# Relay_01.net
KiCad netlist of a schematic drawn in Altium Designer
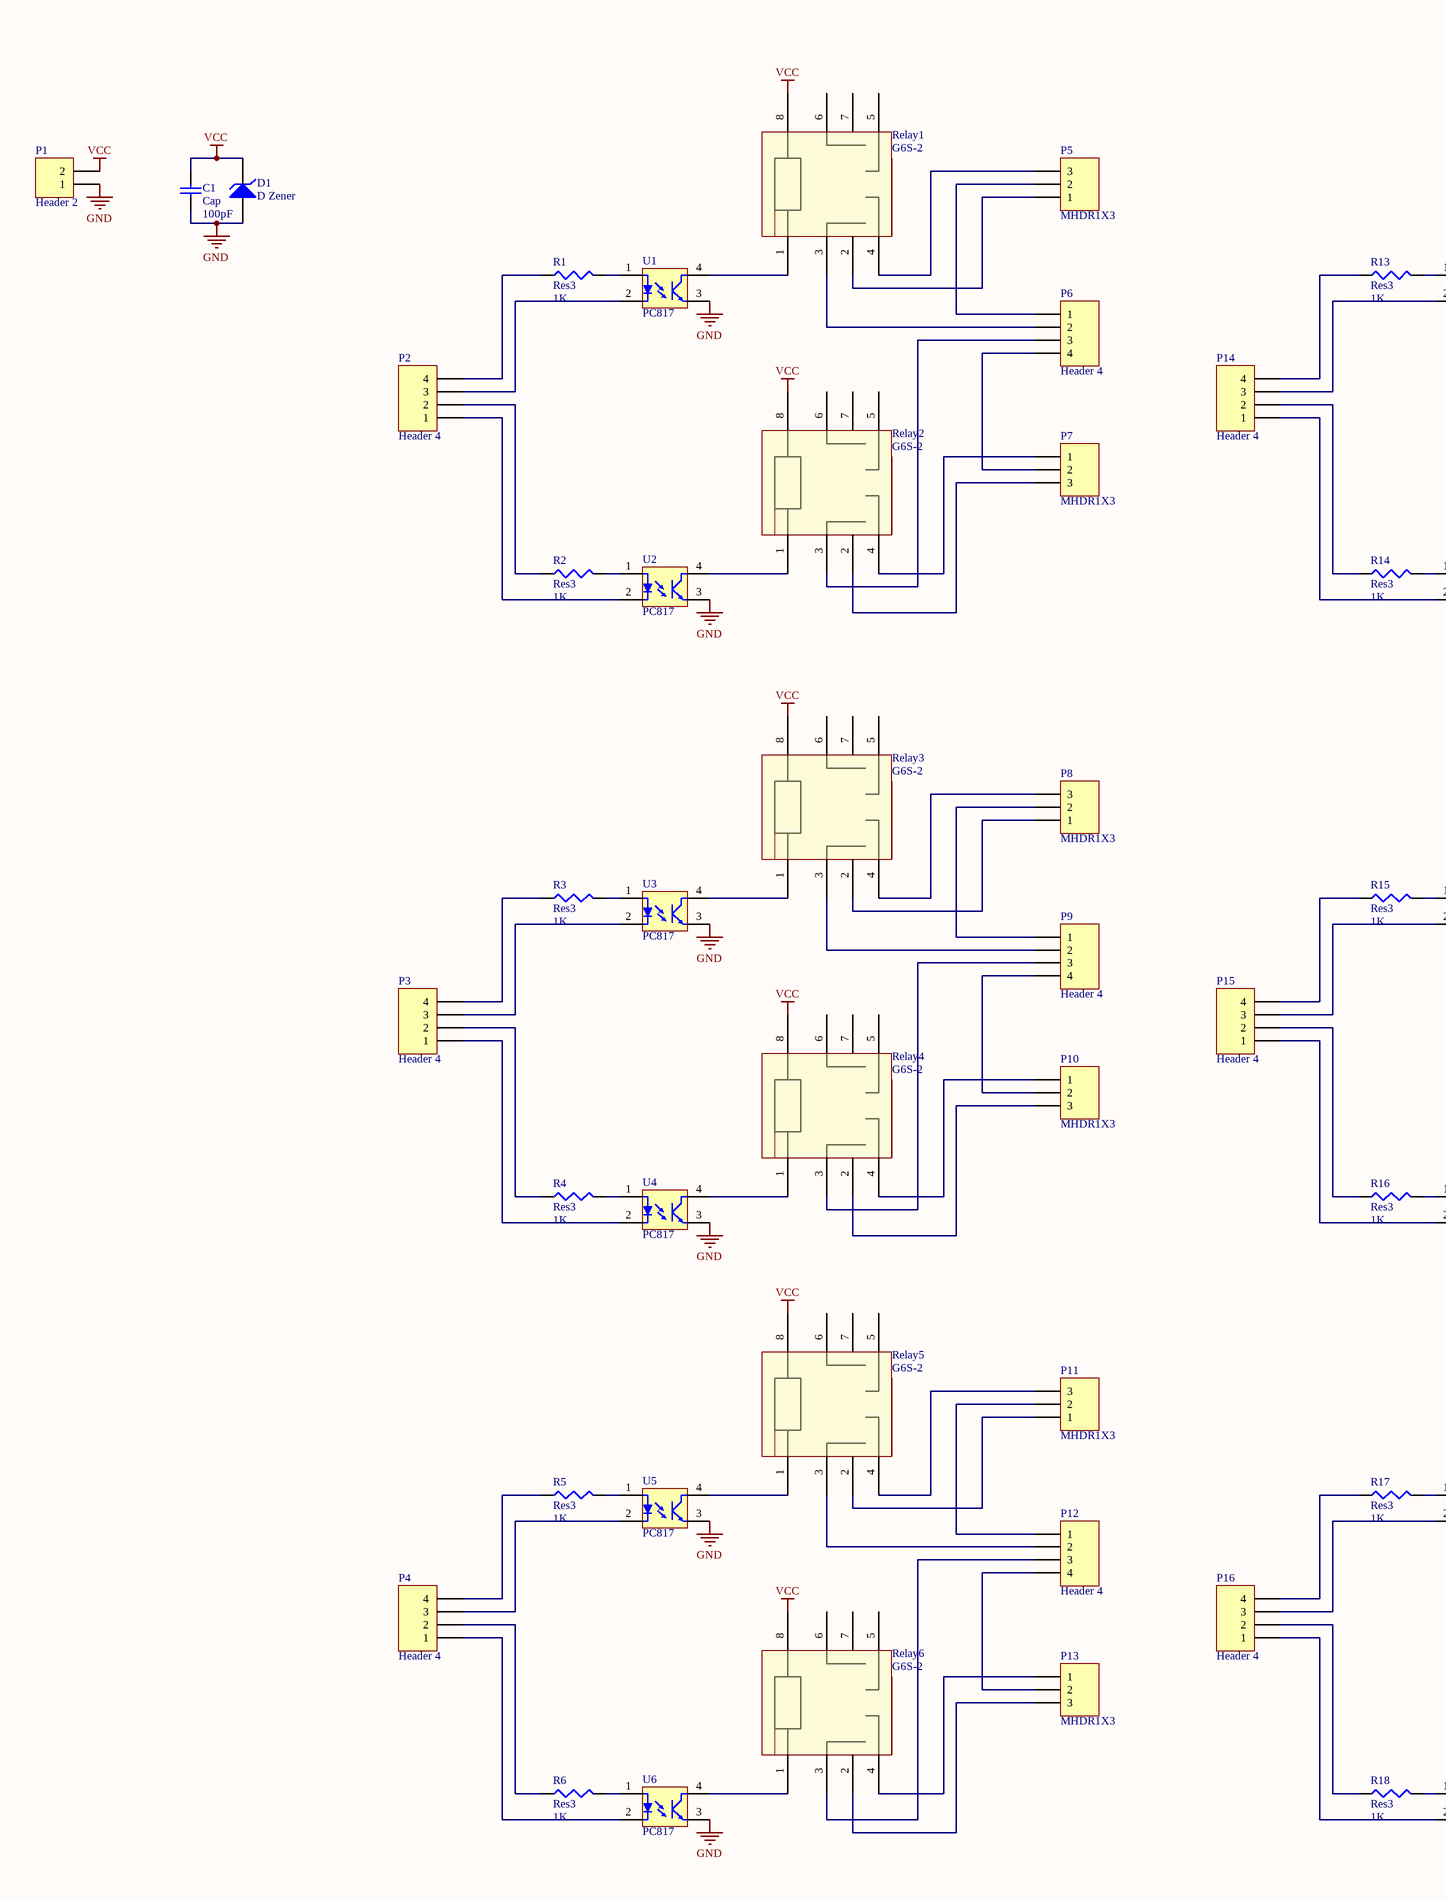
[diagram p0: Relay 01.SchDoc, left]
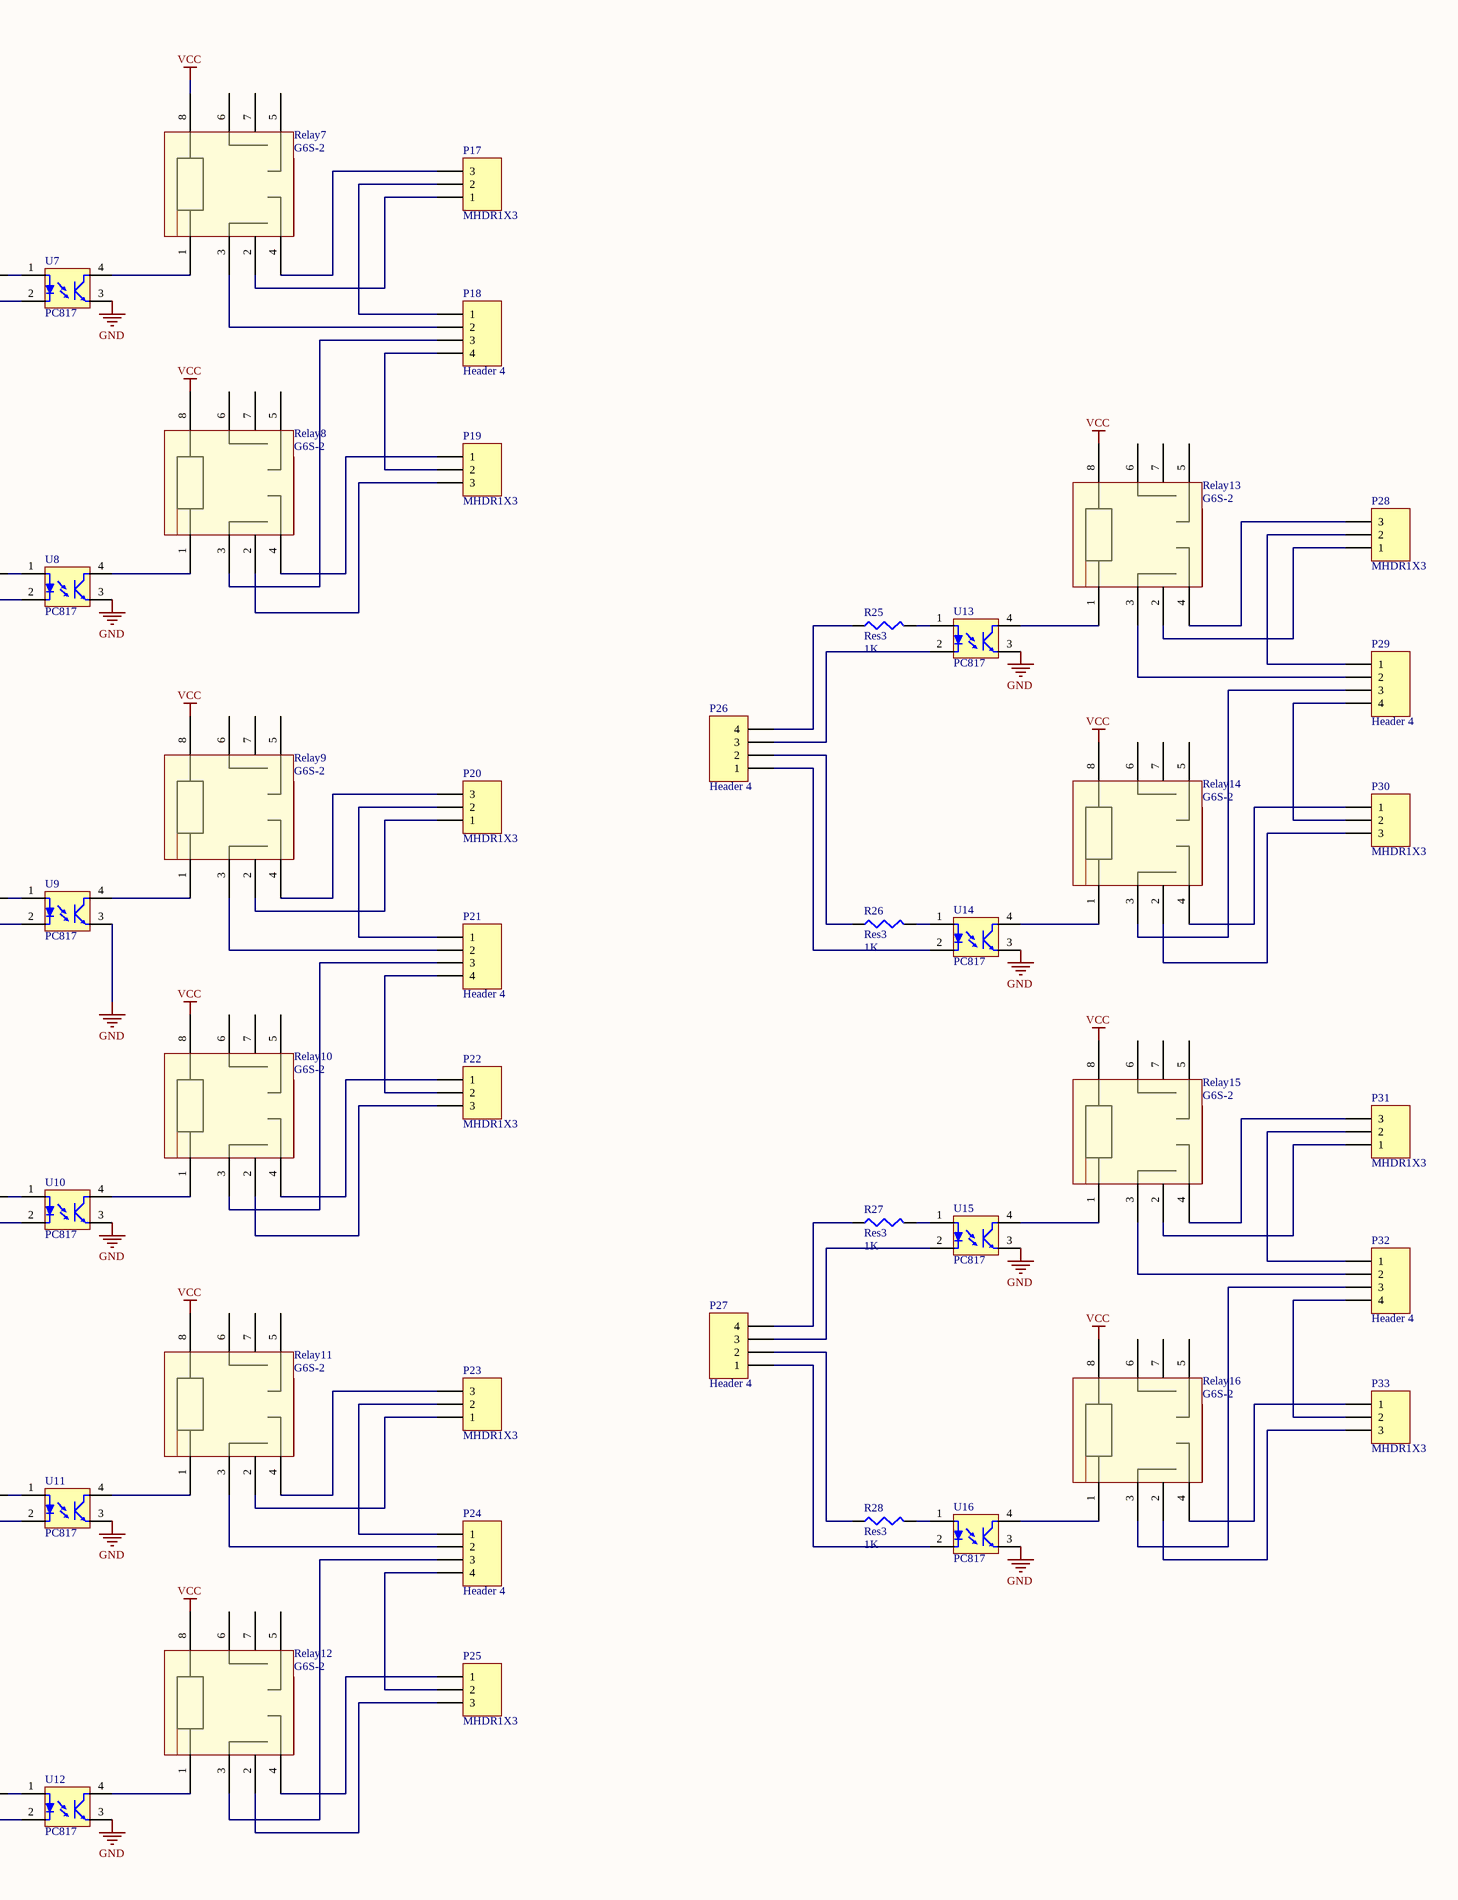
[diagram p1: Relay 01.SchDoc, right]

(export (version "E")
  (design (tool "Eeschema 10.0.6"))
  (components
    (comp (ref "C1")
      (value "Cap")
      (footprint "RAD-0.3")
      (description "Capacitor")
      (fields (field (name "ALTIUM_VALUE") "100pF") (field (name "PUBLISHER") "Altium Limited"))
      (libsource (lib "Miscellaneous Devices") (part "Cap"))
    )
    (comp (ref "D1")
      (value "D Zener")
      (footprint "DIODE-0.7")
      (description "Zener Diode")
      (fields (field (name "PUBLISHER") "Altium Limited"))
      (libsource (lib "Miscellaneous Devices") (part "D Zener"))
    )
    (comp (ref "P1")
      (value "Header 2")
      (footprint "CON2")
      (description "Header, 2-Pin")
      (fields (field (name "PUBLISHER") "Altium Limited"))
      (libsource (lib "Miscellaneous Connectors") (part "Header 2"))
    )
    (comp (ref "P2")
      (value "Header 4")
      (footprint "CON4")
      (description "Header, 4-Pin")
      (fields (field (name "PUBLISHER") "Altium Limited"))
      (libsource (lib "") (part "Header 4_1"))
    )
    (comp (ref "P3")
      (value "Header 4")
      (footprint "CON4")
      (description "Header, 4-Pin")
      (fields (field (name "PUBLISHER") "Altium Limited"))
      (libsource (lib "") (part "Header 4_1"))
    )
    (comp (ref "P4")
      (value "Header 4")
      (footprint "CON4")
      (description "Header, 4-Pin")
      (fields (field (name "PUBLISHER") "Altium Limited"))
      (libsource (lib "") (part "Header 4_1"))
    )
    (comp (ref "P5")
      (value "MHDR1X3")
      (footprint "HDR1X3")
      (description "Header, 3-Pin")
      (fields (field (name "PUBLISHER") "Altium Limited"))
      (libsource (lib "Miscellaneous Connectors") (part "MHDR1X3"))
    )
    (comp (ref "P6")
      (value "Header 4")
      (footprint "CON4")
      (description "Header, 4-Pin")
      (fields (field (name "PUBLISHER") "Altium Limited"))
      (libsource (lib "Miscellaneous Connectors") (part "Header 4"))
    )
    (comp (ref "P7")
      (value "MHDR1X3")
      (footprint "HDR1X3")
      (description "Header, 3-Pin")
      (fields (field (name "PUBLISHER") "Altium Limited"))
      (libsource (lib "") (part "MHDR1X3_1"))
    )
    (comp (ref "P8")
      (value "MHDR1X3")
      (footprint "HDR1X3")
      (description "Header, 3-Pin")
      (fields (field (name "PUBLISHER") "Altium Limited"))
      (libsource (lib "Miscellaneous Connectors") (part "MHDR1X3"))
    )
    (comp (ref "P9")
      (value "Header 4")
      (footprint "CON4")
      (description "Header, 4-Pin")
      (fields (field (name "PUBLISHER") "Altium Limited"))
      (libsource (lib "Miscellaneous Connectors") (part "Header 4"))
    )
    (comp (ref "P10")
      (value "MHDR1X3")
      (footprint "HDR1X3")
      (description "Header, 3-Pin")
      (fields (field (name "PUBLISHER") "Altium Limited"))
      (libsource (lib "") (part "MHDR1X3_1"))
    )
    (comp (ref "P11")
      (value "MHDR1X3")
      (footprint "HDR1X3")
      (description "Header, 3-Pin")
      (fields (field (name "PUBLISHER") "Altium Limited"))
      (libsource (lib "Miscellaneous Connectors") (part "MHDR1X3"))
    )
    (comp (ref "P12")
      (value "Header 4")
      (footprint "CON4")
      (description "Header, 4-Pin")
      (fields (field (name "PUBLISHER") "Altium Limited"))
      (libsource (lib "Miscellaneous Connectors") (part "Header 4"))
    )
    (comp (ref "P13")
      (value "MHDR1X3")
      (footprint "HDR1X3")
      (description "Header, 3-Pin")
      (fields (field (name "PUBLISHER") "Altium Limited"))
      (libsource (lib "") (part "MHDR1X3_1"))
    )
    (comp (ref "P14")
      (value "Header 4")
      (footprint "CON4")
      (description "Header, 4-Pin")
      (fields (field (name "PUBLISHER") "Altium Limited"))
      (libsource (lib "") (part "Header 4_1"))
    )
    (comp (ref "P15")
      (value "Header 4")
      (footprint "CON4")
      (description "Header, 4-Pin")
      (fields (field (name "PUBLISHER") "Altium Limited"))
      (libsource (lib "") (part "Header 4_1"))
    )
    (comp (ref "P16")
      (value "Header 4")
      (footprint "CON4")
      (description "Header, 4-Pin")
      (fields (field (name "PUBLISHER") "Altium Limited"))
      (libsource (lib "") (part "Header 4_1"))
    )
    (comp (ref "P17")
      (value "MHDR1X3")
      (footprint "HDR1X3")
      (description "Header, 3-Pin")
      (fields (field (name "PUBLISHER") "Altium Limited"))
      (libsource (lib "Miscellaneous Connectors") (part "MHDR1X3"))
    )
    (comp (ref "P18")
      (value "Header 4")
      (footprint "CON4")
      (description "Header, 4-Pin")
      (fields (field (name "PUBLISHER") "Altium Limited"))
      (libsource (lib "Miscellaneous Connectors") (part "Header 4"))
    )
    (comp (ref "P19")
      (value "MHDR1X3")
      (footprint "HDR1X3")
      (description "Header, 3-Pin")
      (fields (field (name "PUBLISHER") "Altium Limited"))
      (libsource (lib "") (part "MHDR1X3_1"))
    )
    (comp (ref "P20")
      (value "MHDR1X3")
      (footprint "HDR1X3")
      (description "Header, 3-Pin")
      (fields (field (name "PUBLISHER") "Altium Limited"))
      (libsource (lib "Miscellaneous Connectors") (part "MHDR1X3"))
    )
    (comp (ref "P21")
      (value "Header 4")
      (footprint "CON4")
      (description "Header, 4-Pin")
      (fields (field (name "PUBLISHER") "Altium Limited"))
      (libsource (lib "Miscellaneous Connectors") (part "Header 4"))
    )
    (comp (ref "P22")
      (value "MHDR1X3")
      (footprint "HDR1X3")
      (description "Header, 3-Pin")
      (fields (field (name "PUBLISHER") "Altium Limited"))
      (libsource (lib "") (part "MHDR1X3_1"))
    )
    (comp (ref "P23")
      (value "MHDR1X3")
      (footprint "HDR1X3")
      (description "Header, 3-Pin")
      (fields (field (name "PUBLISHER") "Altium Limited"))
      (libsource (lib "Miscellaneous Connectors") (part "MHDR1X3"))
    )
    (comp (ref "P24")
      (value "Header 4")
      (footprint "CON4")
      (description "Header, 4-Pin")
      (fields (field (name "PUBLISHER") "Altium Limited"))
      (libsource (lib "Miscellaneous Connectors") (part "Header 4"))
    )
    (comp (ref "P25")
      (value "MHDR1X3")
      (footprint "HDR1X3")
      (description "Header, 3-Pin")
      (fields (field (name "PUBLISHER") "Altium Limited"))
      (libsource (lib "") (part "MHDR1X3_1"))
    )
    (comp (ref "P26")
      (value "Header 4")
      (footprint "CON4")
      (description "Header, 4-Pin")
      (fields (field (name "PUBLISHER") "Altium Limited"))
      (libsource (lib "") (part "Header 4_1"))
    )
    (comp (ref "P27")
      (value "Header 4")
      (footprint "CON4")
      (description "Header, 4-Pin")
      (fields (field (name "PUBLISHER") "Altium Limited"))
      (libsource (lib "") (part "Header 4_1"))
    )
    (comp (ref "P28")
      (value "MHDR1X3")
      (footprint "HDR1X3")
      (description "Header, 3-Pin")
      (fields (field (name "PUBLISHER") "Altium Limited"))
      (libsource (lib "Miscellaneous Connectors") (part "MHDR1X3"))
    )
    (comp (ref "P29")
      (value "Header 4")
      (footprint "CON4")
      (description "Header, 4-Pin")
      (fields (field (name "PUBLISHER") "Altium Limited"))
      (libsource (lib "Miscellaneous Connectors") (part "Header 4"))
    )
    (comp (ref "P30")
      (value "MHDR1X3")
      (footprint "HDR1X3")
      (description "Header, 3-Pin")
      (fields (field (name "PUBLISHER") "Altium Limited"))
      (libsource (lib "") (part "MHDR1X3_1"))
    )
    (comp (ref "P31")
      (value "MHDR1X3")
      (footprint "HDR1X3")
      (description "Header, 3-Pin")
      (fields (field (name "PUBLISHER") "Altium Limited"))
      (libsource (lib "Miscellaneous Connectors") (part "MHDR1X3"))
    )
    (comp (ref "P32")
      (value "Header 4")
      (footprint "CON4")
      (description "Header, 4-Pin")
      (fields (field (name "PUBLISHER") "Altium Limited"))
      (libsource (lib "Miscellaneous Connectors") (part "Header 4"))
    )
    (comp (ref "P33")
      (value "MHDR1X3")
      (footprint "HDR1X3")
      (description "Header, 3-Pin")
      (fields (field (name "PUBLISHER") "Altium Limited"))
      (libsource (lib "") (part "MHDR1X3_1"))
    )
    (comp (ref "R1")
      (value "Res3")
      (footprint "R1/4W")
      (description "Resistor")
      (fields (field (name "ALTIUM_VALUE") "1K") (field (name "PUBLISHER") "Altium Limited"))
      (libsource (lib "Miscellaneous Devices") (part "Res3"))
    )
    (comp (ref "R2")
      (value "Res3")
      (footprint "R1/4W")
      (description "Resistor")
      (fields (field (name "ALTIUM_VALUE") "1K") (field (name "PUBLISHER") "Altium Limited"))
      (libsource (lib "Miscellaneous Devices") (part "Res3"))
    )
    (comp (ref "R3")
      (value "Res3")
      (footprint "R1/4W")
      (description "Resistor")
      (fields (field (name "ALTIUM_VALUE") "1K") (field (name "PUBLISHER") "Altium Limited"))
      (libsource (lib "Miscellaneous Devices") (part "Res3"))
    )
    (comp (ref "R4")
      (value "Res3")
      (footprint "R1/4W")
      (description "Resistor")
      (fields (field (name "ALTIUM_VALUE") "1K") (field (name "PUBLISHER") "Altium Limited"))
      (libsource (lib "Miscellaneous Devices") (part "Res3"))
    )
    (comp (ref "R5")
      (value "Res3")
      (footprint "R1/4W")
      (description "Resistor")
      (fields (field (name "ALTIUM_VALUE") "1K") (field (name "PUBLISHER") "Altium Limited"))
      (libsource (lib "Miscellaneous Devices") (part "Res3"))
    )
    (comp (ref "R6")
      (value "Res3")
      (footprint "R1/4W")
      (description "Resistor")
      (fields (field (name "ALTIUM_VALUE") "1K") (field (name "PUBLISHER") "Altium Limited"))
      (libsource (lib "Miscellaneous Devices") (part "Res3"))
    )
    (comp (ref "R13")
      (value "Res3")
      (footprint "R1/4W")
      (description "Resistor")
      (fields (field (name "ALTIUM_VALUE") "1K") (field (name "PUBLISHER") "Altium Limited"))
      (libsource (lib "Miscellaneous Devices") (part "Res3"))
    )
    (comp (ref "R14")
      (value "Res3")
      (footprint "R1/4W")
      (description "Resistor")
      (fields (field (name "ALTIUM_VALUE") "1K") (field (name "PUBLISHER") "Altium Limited"))
      (libsource (lib "Miscellaneous Devices") (part "Res3"))
    )
    (comp (ref "R15")
      (value "Res3")
      (footprint "R1/4W")
      (description "Resistor")
      (fields (field (name "ALTIUM_VALUE") "1K") (field (name "PUBLISHER") "Altium Limited"))
      (libsource (lib "Miscellaneous Devices") (part "Res3"))
    )
    (comp (ref "R16")
      (value "Res3")
      (footprint "R1/4W")
      (description "Resistor")
      (fields (field (name "ALTIUM_VALUE") "1K") (field (name "PUBLISHER") "Altium Limited"))
      (libsource (lib "Miscellaneous Devices") (part "Res3"))
    )
    (comp (ref "R17")
      (value "Res3")
      (footprint "R1/4W")
      (description "Resistor")
      (fields (field (name "ALTIUM_VALUE") "1K") (field (name "PUBLISHER") "Altium Limited"))
      (libsource (lib "Miscellaneous Devices") (part "Res3"))
    )
    (comp (ref "R18")
      (value "Res3")
      (footprint "R1/4W")
      (description "Resistor")
      (fields (field (name "ALTIUM_VALUE") "1K") (field (name "PUBLISHER") "Altium Limited"))
      (libsource (lib "Miscellaneous Devices") (part "Res3"))
    )
    (comp (ref "R25")
      (value "Res3")
      (footprint "R1/4W")
      (description "Resistor")
      (fields (field (name "ALTIUM_VALUE") "1K") (field (name "PUBLISHER") "Altium Limited"))
      (libsource (lib "Miscellaneous Devices") (part "Res3"))
    )
    (comp (ref "R26")
      (value "Res3")
      (footprint "R1/4W")
      (description "Resistor")
      (fields (field (name "ALTIUM_VALUE") "1K") (field (name "PUBLISHER") "Altium Limited"))
      (libsource (lib "Miscellaneous Devices") (part "Res3"))
    )
    (comp (ref "R27")
      (value "Res3")
      (footprint "R1/4W")
      (description "Resistor")
      (fields (field (name "ALTIUM_VALUE") "1K") (field (name "PUBLISHER") "Altium Limited"))
      (libsource (lib "Miscellaneous Devices") (part "Res3"))
    )
    (comp (ref "R28")
      (value "Res3")
      (footprint "R1/4W")
      (description "Resistor")
      (fields (field (name "ALTIUM_VALUE") "1K") (field (name "PUBLISHER") "Altium Limited"))
      (libsource (lib "Miscellaneous Devices") (part "Res3"))
    )
    (comp (ref "Relay1")
      (value "G6S-2")
      (footprint "G6S-2")
      (libsource (lib "dung_maker_2018") (part "G6S-2"))
    )
    (comp (ref "Relay2")
      (value "G6S-2")
      (footprint "G6S-2")
      (libsource (lib "dung_maker_2018") (part "G6S-2"))
    )
    (comp (ref "Relay3")
      (value "G6S-2")
      (footprint "G6S-2")
      (libsource (lib "dung_maker_2018") (part "G6S-2"))
    )
    (comp (ref "Relay4")
      (value "G6S-2")
      (footprint "G6S-2")
      (libsource (lib "dung_maker_2018") (part "G6S-2"))
    )
    (comp (ref "Relay5")
      (value "G6S-2")
      (footprint "G6S-2")
      (libsource (lib "dung_maker_2018") (part "G6S-2"))
    )
    (comp (ref "Relay6")
      (value "G6S-2")
      (footprint "G6S-2")
      (libsource (lib "dung_maker_2018") (part "G6S-2"))
    )
    (comp (ref "Relay7")
      (value "G6S-2")
      (footprint "G6S-2")
      (libsource (lib "dung_maker_2018") (part "G6S-2"))
    )
    (comp (ref "Relay8")
      (value "G6S-2")
      (footprint "G6S-2")
      (libsource (lib "dung_maker_2018") (part "G6S-2"))
    )
    (comp (ref "Relay9")
      (value "G6S-2")
      (footprint "G6S-2")
      (libsource (lib "dung_maker_2018") (part "G6S-2"))
    )
    (comp (ref "Relay10")
      (value "G6S-2")
      (footprint "G6S-2")
      (libsource (lib "dung_maker_2018") (part "G6S-2"))
    )
    (comp (ref "Relay11")
      (value "G6S-2")
      (footprint "G6S-2")
      (libsource (lib "dung_maker_2018") (part "G6S-2"))
    )
    (comp (ref "Relay12")
      (value "G6S-2")
      (footprint "G6S-2")
      (libsource (lib "dung_maker_2018") (part "G6S-2"))
    )
    (comp (ref "Relay13")
      (value "G6S-2")
      (footprint "G6S-2")
      (libsource (lib "dung_maker_2018") (part "G6S-2"))
    )
    (comp (ref "Relay14")
      (value "G6S-2")
      (footprint "G6S-2")
      (libsource (lib "dung_maker_2018") (part "G6S-2"))
    )
    (comp (ref "Relay15")
      (value "G6S-2")
      (footprint "G6S-2")
      (libsource (lib "dung_maker_2018") (part "G6S-2"))
    )
    (comp (ref "Relay16")
      (value "G6S-2")
      (footprint "G6S-2")
      (libsource (lib "dung_maker_2018") (part "G6S-2"))
    )
    (comp (ref "U1")
      (value "PC817")
      (footprint "DIP4")
      (fields (field (name "Comment") "OPTO"))
      (libsource (lib "dung_maker_2018") (part "OPTO_PC817"))
    )
    (comp (ref "U2")
      (value "PC817")
      (footprint "DIP4")
      (fields (field (name "Comment") "OPTO"))
      (libsource (lib "dung_maker_2018") (part "OPTO_PC817"))
    )
    (comp (ref "U3")
      (value "PC817")
      (footprint "DIP4")
      (fields (field (name "Comment") "OPTO"))
      (libsource (lib "dung_maker_2018") (part "OPTO_PC817"))
    )
    (comp (ref "U4")
      (value "PC817")
      (footprint "DIP4")
      (fields (field (name "Comment") "OPTO"))
      (libsource (lib "dung_maker_2018") (part "OPTO_PC817"))
    )
    (comp (ref "U5")
      (value "PC817")
      (footprint "DIP4")
      (fields (field (name "Comment") "OPTO"))
      (libsource (lib "dung_maker_2018") (part "OPTO_PC817"))
    )
    (comp (ref "U6")
      (value "PC817")
      (footprint "DIP4")
      (fields (field (name "Comment") "OPTO"))
      (libsource (lib "dung_maker_2018") (part "OPTO_PC817"))
    )
    (comp (ref "U7")
      (value "PC817")
      (footprint "DIP4")
      (fields (field (name "Comment") "OPTO"))
      (libsource (lib "dung_maker_2018") (part "OPTO_PC817"))
    )
    (comp (ref "U8")
      (value "PC817")
      (footprint "DIP4")
      (fields (field (name "Comment") "OPTO"))
      (libsource (lib "dung_maker_2018") (part "OPTO_PC817"))
    )
    (comp (ref "U9")
      (value "PC817")
      (footprint "DIP4")
      (fields (field (name "Comment") "OPTO"))
      (libsource (lib "dung_maker_2018") (part "OPTO_PC817"))
    )
    (comp (ref "U10")
      (value "PC817")
      (footprint "DIP4")
      (fields (field (name "Comment") "OPTO"))
      (libsource (lib "dung_maker_2018") (part "OPTO_PC817"))
    )
    (comp (ref "U11")
      (value "PC817")
      (footprint "DIP4")
      (fields (field (name "Comment") "OPTO"))
      (libsource (lib "dung_maker_2018") (part "OPTO_PC817"))
    )
    (comp (ref "U12")
      (value "PC817")
      (footprint "DIP4")
      (fields (field (name "Comment") "OPTO"))
      (libsource (lib "dung_maker_2018") (part "OPTO_PC817"))
    )
    (comp (ref "U13")
      (value "PC817")
      (footprint "DIP4")
      (fields (field (name "Comment") "OPTO"))
      (libsource (lib "dung_maker_2018") (part "OPTO_PC817"))
    )
    (comp (ref "U14")
      (value "PC817")
      (footprint "DIP4")
      (fields (field (name "Comment") "OPTO"))
      (libsource (lib "dung_maker_2018") (part "OPTO_PC817"))
    )
    (comp (ref "U15")
      (value "PC817")
      (footprint "DIP4")
      (fields (field (name "Comment") "OPTO"))
      (libsource (lib "dung_maker_2018") (part "OPTO_PC817"))
    )
    (comp (ref "U16")
      (value "PC817")
      (footprint "DIP4")
      (fields (field (name "Comment") "OPTO"))
      (libsource (lib "dung_maker_2018") (part "OPTO_PC817"))
    )
  )
  (nets
    (net (code "1") (name "GND") (class "Default")
      (node (ref "C1") (pin "1") (pinfunction "1_1") (pintype "passive"))
      (node (ref "D1") (pin "1") (pinfunction "A_1") (pintype "passive"))
      (node (ref "P1") (pin "1") (pinfunction "1_1") (pintype "passive"))
      (node (ref "U1") (pin "3") (pinfunction "E_3") (pintype "passive"))
      (node (ref "U10") (pin "3") (pinfunction "E_3") (pintype "passive"))
      (node (ref "U11") (pin "3") (pinfunction "E_3") (pintype "passive"))
      (node (ref "U12") (pin "3") (pinfunction "E_3") (pintype "passive"))
      (node (ref "U13") (pin "3") (pinfunction "E_3") (pintype "passive"))
      (node (ref "U14") (pin "3") (pinfunction "E_3") (pintype "passive"))
      (node (ref "U15") (pin "3") (pinfunction "E_3") (pintype "passive"))
      (node (ref "U16") (pin "3") (pinfunction "E_3") (pintype "passive"))
      (node (ref "U2") (pin "3") (pinfunction "E_3") (pintype "passive"))
      (node (ref "U3") (pin "3") (pinfunction "E_3") (pintype "passive"))
      (node (ref "U4") (pin "3") (pinfunction "E_3") (pintype "passive"))
      (node (ref "U5") (pin "3") (pinfunction "E_3") (pintype "passive"))
      (node (ref "U6") (pin "3") (pinfunction "E_3") (pintype "passive"))
      (node (ref "U7") (pin "3") (pinfunction "E_3") (pintype "passive"))
      (node (ref "U8") (pin "3") (pinfunction "E_3") (pintype "passive"))
      (node (ref "U9") (pin "3") (pinfunction "E_3") (pintype "passive"))
    )
    (net (code "2") (name "Net-(P2-Pad1)") (class "Default")
      (node (ref "P2") (pin "1") (pinfunction "1_1") (pintype "passive"))
      (node (ref "U2") (pin "2") (pinfunction "C_2") (pintype "passive"))
    )
    (net (code "3") (name "Net-(P2-Pad2)") (class "Default")
      (node (ref "P2") (pin "2") (pinfunction "2_2") (pintype "passive"))
      (node (ref "R2") (pin "1") (pinfunction "1_1") (pintype "passive"))
    )
    (net (code "4") (name "Net-(P2-Pad3)") (class "Default")
      (node (ref "P2") (pin "3") (pinfunction "3_3") (pintype "passive"))
      (node (ref "U1") (pin "2") (pinfunction "C_2") (pintype "passive"))
    )
    (net (code "5") (name "Net-(P2-Pad4)") (class "Default")
      (node (ref "P2") (pin "4") (pinfunction "4_4") (pintype "passive"))
      (node (ref "R1") (pin "1") (pinfunction "1_1") (pintype "passive"))
    )
    (net (code "6") (name "Net-(P3-Pad1)") (class "Default")
      (node (ref "P3") (pin "1") (pinfunction "1_1") (pintype "passive"))
      (node (ref "U4") (pin "2") (pinfunction "C_2") (pintype "passive"))
    )
    (net (code "7") (name "Net-(P3-Pad2)") (class "Default")
      (node (ref "P3") (pin "2") (pinfunction "2_2") (pintype "passive"))
      (node (ref "R4") (pin "1") (pinfunction "1_1") (pintype "passive"))
    )
    (net (code "8") (name "Net-(P3-Pad3)") (class "Default")
      (node (ref "P3") (pin "3") (pinfunction "3_3") (pintype "passive"))
      (node (ref "U3") (pin "2") (pinfunction "C_2") (pintype "passive"))
    )
    (net (code "9") (name "Net-(P3-Pad4)") (class "Default")
      (node (ref "P3") (pin "4") (pinfunction "4_4") (pintype "passive"))
      (node (ref "R3") (pin "1") (pinfunction "1_1") (pintype "passive"))
    )
    (net (code "10") (name "Net-(P4-Pad1)") (class "Default")
      (node (ref "P4") (pin "1") (pinfunction "1_1") (pintype "passive"))
      (node (ref "U6") (pin "2") (pinfunction "C_2") (pintype "passive"))
    )
    (net (code "11") (name "Net-(P4-Pad2)") (class "Default")
      (node (ref "P4") (pin "2") (pinfunction "2_2") (pintype "passive"))
      (node (ref "R6") (pin "1") (pinfunction "1_1") (pintype "passive"))
    )
    (net (code "12") (name "Net-(P4-Pad3)") (class "Default")
      (node (ref "P4") (pin "3") (pinfunction "3_3") (pintype "passive"))
      (node (ref "U5") (pin "2") (pinfunction "C_2") (pintype "passive"))
    )
    (net (code "13") (name "Net-(P4-Pad4)") (class "Default")
      (node (ref "P4") (pin "4") (pinfunction "4_4") (pintype "passive"))
      (node (ref "R5") (pin "1") (pinfunction "1_1") (pintype "passive"))
    )
    (net (code "14") (name "Net-(P5-Pad2)") (class "Default")
      (node (ref "P5") (pin "2") (pinfunction "2_2") (pintype "passive"))
      (node (ref "P6") (pin "1") (pinfunction "1_1") (pintype "passive"))
    )
    (net (code "15") (name "Net-(P6-Pad2)") (class "Default")
      (node (ref "P6") (pin "2") (pinfunction "2_2") (pintype "passive"))
      (node (ref "Relay1") (pin "3") (pinfunction "3_3") (pintype "passive"))
    )
    (net (code "16") (name "Net-(P6-Pad3)") (class "Default")
      (node (ref "P6") (pin "3") (pinfunction "3_3") (pintype "passive"))
      (node (ref "Relay2") (pin "3") (pinfunction "3_3") (pintype "passive"))
    )
    (net (code "17") (name "Net-(P6-Pad4)") (class "Default")
      (node (ref "P6") (pin "4") (pinfunction "4_4") (pintype "passive"))
      (node (ref "P7") (pin "2") (pinfunction "2_2") (pintype "passive"))
    )
    (net (code "18") (name "Net-(P8-Pad2)") (class "Default")
      (node (ref "P8") (pin "2") (pinfunction "2_2") (pintype "passive"))
      (node (ref "P9") (pin "1") (pinfunction "1_1") (pintype "passive"))
    )
    (net (code "19") (name "Net-(P9-Pad2)") (class "Default")
      (node (ref "P9") (pin "2") (pinfunction "2_2") (pintype "passive"))
      (node (ref "Relay3") (pin "3") (pinfunction "3_3") (pintype "passive"))
    )
    (net (code "20") (name "Net-(P9-Pad3)") (class "Default")
      (node (ref "P9") (pin "3") (pinfunction "3_3") (pintype "passive"))
      (node (ref "Relay4") (pin "3") (pinfunction "3_3") (pintype "passive"))
    )
    (net (code "21") (name "Net-(P10-Pad2)") (class "Default")
      (node (ref "P10") (pin "2") (pinfunction "2_2") (pintype "passive"))
      (node (ref "P9") (pin "4") (pinfunction "4_4") (pintype "passive"))
    )
    (net (code "22") (name "Net-(P11-Pad2)") (class "Default")
      (node (ref "P11") (pin "2") (pinfunction "2_2") (pintype "passive"))
      (node (ref "P12") (pin "1") (pinfunction "1_1") (pintype "passive"))
    )
    (net (code "23") (name "Net-(P12-Pad2)") (class "Default")
      (node (ref "P12") (pin "2") (pinfunction "2_2") (pintype "passive"))
      (node (ref "Relay5") (pin "3") (pinfunction "3_3") (pintype "passive"))
    )
    (net (code "24") (name "Net-(P12-Pad3)") (class "Default")
      (node (ref "P12") (pin "3") (pinfunction "3_3") (pintype "passive"))
      (node (ref "Relay6") (pin "3") (pinfunction "3_3") (pintype "passive"))
    )
    (net (code "25") (name "Net-(P12-Pad4)") (class "Default")
      (node (ref "P12") (pin "4") (pinfunction "4_4") (pintype "passive"))
      (node (ref "P13") (pin "2") (pinfunction "2_2") (pintype "passive"))
    )
    (net (code "26") (name "Net-(P14-Pad1)") (class "Default")
      (node (ref "P14") (pin "1") (pinfunction "1_1") (pintype "passive"))
      (node (ref "U8") (pin "2") (pinfunction "C_2") (pintype "passive"))
    )
    (net (code "27") (name "Net-(P14-Pad2)") (class "Default")
      (node (ref "P14") (pin "2") (pinfunction "2_2") (pintype "passive"))
      (node (ref "R14") (pin "1") (pinfunction "1_1") (pintype "passive"))
    )
    (net (code "28") (name "Net-(P14-Pad3)") (class "Default")
      (node (ref "P14") (pin "3") (pinfunction "3_3") (pintype "passive"))
      (node (ref "U7") (pin "2") (pinfunction "C_2") (pintype "passive"))
    )
    (net (code "29") (name "Net-(P14-Pad4)") (class "Default")
      (node (ref "P14") (pin "4") (pinfunction "4_4") (pintype "passive"))
      (node (ref "R13") (pin "1") (pinfunction "1_1") (pintype "passive"))
    )
    (net (code "30") (name "Net-(P15-Pad1)") (class "Default")
      (node (ref "P15") (pin "1") (pinfunction "1_1") (pintype "passive"))
      (node (ref "U10") (pin "2") (pinfunction "C_2") (pintype "passive"))
    )
    (net (code "31") (name "Net-(P15-Pad2)") (class "Default")
      (node (ref "P15") (pin "2") (pinfunction "2_2") (pintype "passive"))
      (node (ref "R16") (pin "1") (pinfunction "1_1") (pintype "passive"))
    )
    (net (code "32") (name "Net-(P15-Pad3)") (class "Default")
      (node (ref "P15") (pin "3") (pinfunction "3_3") (pintype "passive"))
      (node (ref "U9") (pin "2") (pinfunction "C_2") (pintype "passive"))
    )
    (net (code "33") (name "Net-(P15-Pad4)") (class "Default")
      (node (ref "P15") (pin "4") (pinfunction "4_4") (pintype "passive"))
      (node (ref "R15") (pin "1") (pinfunction "1_1") (pintype "passive"))
    )
    (net (code "34") (name "Net-(P16-Pad1)") (class "Default")
      (node (ref "P16") (pin "1") (pinfunction "1_1") (pintype "passive"))
      (node (ref "U12") (pin "2") (pinfunction "C_2") (pintype "passive"))
    )
    (net (code "35") (name "Net-(P16-Pad2)") (class "Default")
      (node (ref "P16") (pin "2") (pinfunction "2_2") (pintype "passive"))
      (node (ref "R18") (pin "1") (pinfunction "1_1") (pintype "passive"))
    )
    (net (code "36") (name "Net-(P16-Pad3)") (class "Default")
      (node (ref "P16") (pin "3") (pinfunction "3_3") (pintype "passive"))
      (node (ref "U11") (pin "2") (pinfunction "C_2") (pintype "passive"))
    )
    (net (code "37") (name "Net-(P16-Pad4)") (class "Default")
      (node (ref "P16") (pin "4") (pinfunction "4_4") (pintype "passive"))
      (node (ref "R17") (pin "1") (pinfunction "1_1") (pintype "passive"))
    )
    (net (code "38") (name "Net-(P17-Pad2)") (class "Default")
      (node (ref "P17") (pin "2") (pinfunction "2_2") (pintype "passive"))
      (node (ref "P18") (pin "1") (pinfunction "1_1") (pintype "passive"))
    )
    (net (code "39") (name "Net-(P18-Pad2)") (class "Default")
      (node (ref "P18") (pin "2") (pinfunction "2_2") (pintype "passive"))
      (node (ref "Relay7") (pin "3") (pinfunction "3_3") (pintype "passive"))
    )
    (net (code "40") (name "Net-(P18-Pad3)") (class "Default")
      (node (ref "P18") (pin "3") (pinfunction "3_3") (pintype "passive"))
      (node (ref "Relay8") (pin "3") (pinfunction "3_3") (pintype "passive"))
    )
    (net (code "41") (name "Net-(P18-Pad4)") (class "Default")
      (node (ref "P18") (pin "4") (pinfunction "4_4") (pintype "passive"))
      (node (ref "P19") (pin "2") (pinfunction "2_2") (pintype "passive"))
    )
    (net (code "42") (name "Net-(P20-Pad2)") (class "Default")
      (node (ref "P20") (pin "2") (pinfunction "2_2") (pintype "passive"))
      (node (ref "P21") (pin "1") (pinfunction "1_1") (pintype "passive"))
    )
    (net (code "43") (name "Net-(P21-Pad2)") (class "Default")
      (node (ref "P21") (pin "2") (pinfunction "2_2") (pintype "passive"))
      (node (ref "Relay9") (pin "3") (pinfunction "3_3") (pintype "passive"))
    )
    (net (code "44") (name "Net-(P21-Pad3)") (class "Default")
      (node (ref "P21") (pin "3") (pinfunction "3_3") (pintype "passive"))
      (node (ref "Relay10") (pin "3") (pinfunction "3_3") (pintype "passive"))
    )
    (net (code "45") (name "Net-(P21-Pad4)") (class "Default")
      (node (ref "P21") (pin "4") (pinfunction "4_4") (pintype "passive"))
      (node (ref "P22") (pin "2") (pinfunction "2_2") (pintype "passive"))
    )
    (net (code "46") (name "Net-(P23-Pad2)") (class "Default")
      (node (ref "P23") (pin "2") (pinfunction "2_2") (pintype "passive"))
      (node (ref "P24") (pin "1") (pinfunction "1_1") (pintype "passive"))
    )
    (net (code "47") (name "Net-(P24-Pad2)") (class "Default")
      (node (ref "P24") (pin "2") (pinfunction "2_2") (pintype "passive"))
      (node (ref "Relay11") (pin "3") (pinfunction "3_3") (pintype "passive"))
    )
    (net (code "48") (name "Net-(P24-Pad3)") (class "Default")
      (node (ref "P24") (pin "3") (pinfunction "3_3") (pintype "passive"))
      (node (ref "Relay12") (pin "3") (pinfunction "3_3") (pintype "passive"))
    )
    (net (code "49") (name "Net-(P24-Pad4)") (class "Default")
      (node (ref "P24") (pin "4") (pinfunction "4_4") (pintype "passive"))
      (node (ref "P25") (pin "2") (pinfunction "2_2") (pintype "passive"))
    )
    (net (code "50") (name "Net-(P26-Pad1)") (class "Default")
      (node (ref "P26") (pin "1") (pinfunction "1_1") (pintype "passive"))
      (node (ref "U14") (pin "2") (pinfunction "C_2") (pintype "passive"))
    )
    (net (code "51") (name "Net-(P26-Pad2)") (class "Default")
      (node (ref "P26") (pin "2") (pinfunction "2_2") (pintype "passive"))
      (node (ref "R26") (pin "1") (pinfunction "1_1") (pintype "passive"))
    )
    (net (code "52") (name "Net-(P26-Pad3)") (class "Default")
      (node (ref "P26") (pin "3") (pinfunction "3_3") (pintype "passive"))
      (node (ref "U13") (pin "2") (pinfunction "C_2") (pintype "passive"))
    )
    (net (code "53") (name "Net-(P26-Pad4)") (class "Default")
      (node (ref "P26") (pin "4") (pinfunction "4_4") (pintype "passive"))
      (node (ref "R25") (pin "1") (pinfunction "1_1") (pintype "passive"))
    )
    (net (code "54") (name "Net-(P27-Pad1)") (class "Default")
      (node (ref "P27") (pin "1") (pinfunction "1_1") (pintype "passive"))
      (node (ref "U16") (pin "2") (pinfunction "C_2") (pintype "passive"))
    )
    (net (code "55") (name "Net-(P27-Pad2)") (class "Default")
      (node (ref "P27") (pin "2") (pinfunction "2_2") (pintype "passive"))
      (node (ref "R28") (pin "1") (pinfunction "1_1") (pintype "passive"))
    )
    (net (code "56") (name "Net-(P27-Pad3)") (class "Default")
      (node (ref "P27") (pin "3") (pinfunction "3_3") (pintype "passive"))
      (node (ref "U15") (pin "2") (pinfunction "C_2") (pintype "passive"))
    )
    (net (code "57") (name "Net-(P27-Pad4)") (class "Default")
      (node (ref "P27") (pin "4") (pinfunction "4_4") (pintype "passive"))
      (node (ref "R27") (pin "1") (pinfunction "1_1") (pintype "passive"))
    )
    (net (code "58") (name "Net-(P28-Pad2)") (class "Default")
      (node (ref "P28") (pin "2") (pinfunction "2_2") (pintype "passive"))
      (node (ref "P29") (pin "1") (pinfunction "1_1") (pintype "passive"))
    )
    (net (code "59") (name "Net-(P29-Pad2)") (class "Default")
      (node (ref "P29") (pin "2") (pinfunction "2_2") (pintype "passive"))
      (node (ref "Relay13") (pin "3") (pinfunction "3_3") (pintype "passive"))
    )
    (net (code "60") (name "Net-(P29-Pad3)") (class "Default")
      (node (ref "P29") (pin "3") (pinfunction "3_3") (pintype "passive"))
      (node (ref "Relay14") (pin "3") (pinfunction "3_3") (pintype "passive"))
    )
    (net (code "61") (name "Net-(P29-Pad4)") (class "Default")
      (node (ref "P29") (pin "4") (pinfunction "4_4") (pintype "passive"))
      (node (ref "P30") (pin "2") (pinfunction "2_2") (pintype "passive"))
    )
    (net (code "62") (name "Net-(P31-Pad2)") (class "Default")
      (node (ref "P31") (pin "2") (pinfunction "2_2") (pintype "passive"))
      (node (ref "P32") (pin "1") (pinfunction "1_1") (pintype "passive"))
    )
    (net (code "63") (name "Net-(P32-Pad2)") (class "Default")
      (node (ref "P32") (pin "2") (pinfunction "2_2") (pintype "passive"))
      (node (ref "Relay15") (pin "3") (pinfunction "3_3") (pintype "passive"))
    )
    (net (code "64") (name "Net-(P32-Pad3)") (class "Default")
      (node (ref "P32") (pin "3") (pinfunction "3_3") (pintype "passive"))
      (node (ref "Relay16") (pin "3") (pinfunction "3_3") (pintype "passive"))
    )
    (net (code "65") (name "Net-(P32-Pad4)") (class "Default")
      (node (ref "P32") (pin "4") (pinfunction "4_4") (pintype "passive"))
      (node (ref "P33") (pin "2") (pinfunction "2_2") (pintype "passive"))
    )
    (net (code "66") (name "Net-(Relay1-NC)") (class "Default")
      (node (ref "P5") (pin "1") (pinfunction "1_1") (pintype "passive"))
      (node (ref "Relay1") (pin "2") (pinfunction "NC_2") (pintype "passive"))
    )
    (net (code "67") (name "Net-(Relay1-NO)") (class "Default")
      (node (ref "P5") (pin "3") (pinfunction "3_3") (pintype "passive"))
      (node (ref "Relay1") (pin "4") (pinfunction "NO_4") (pintype "passive"))
    )
    (net (code "68") (name "Net-(Relay1-Pad1)") (class "Default")
      (node (ref "Relay1") (pin "1") (pinfunction "1_1") (pintype "passive"))
      (node (ref "U1") (pin "4") (pinfunction "C_4") (pintype "passive"))
    )
    (net (code "69") (name "Net-(Relay2-NC)") (class "Default")
      (node (ref "P7") (pin "3") (pinfunction "3_3") (pintype "passive"))
      (node (ref "Relay2") (pin "2") (pinfunction "NC_2") (pintype "passive"))
    )
    (net (code "70") (name "Net-(Relay2-NO)") (class "Default")
      (node (ref "P7") (pin "1") (pinfunction "1_1") (pintype "passive"))
      (node (ref "Relay2") (pin "4") (pinfunction "NO_4") (pintype "passive"))
    )
    (net (code "71") (name "Net-(Relay2-Pad1)") (class "Default")
      (node (ref "Relay2") (pin "1") (pinfunction "1_1") (pintype "passive"))
      (node (ref "U2") (pin "4") (pinfunction "C_4") (pintype "passive"))
    )
    (net (code "72") (name "Net-(Relay3-NC)") (class "Default")
      (node (ref "P8") (pin "1") (pinfunction "1_1") (pintype "passive"))
      (node (ref "Relay3") (pin "2") (pinfunction "NC_2") (pintype "passive"))
    )
    (net (code "73") (name "Net-(Relay3-NO)") (class "Default")
      (node (ref "P8") (pin "3") (pinfunction "3_3") (pintype "passive"))
      (node (ref "Relay3") (pin "4") (pinfunction "NO_4") (pintype "passive"))
    )
    (net (code "74") (name "Net-(Relay3-Pad1)") (class "Default")
      (node (ref "Relay3") (pin "1") (pinfunction "1_1") (pintype "passive"))
      (node (ref "U3") (pin "4") (pinfunction "C_4") (pintype "passive"))
    )
    (net (code "75") (name "Net-(Relay4-NC)") (class "Default")
      (node (ref "P10") (pin "3") (pinfunction "3_3") (pintype "passive"))
      (node (ref "Relay4") (pin "2") (pinfunction "NC_2") (pintype "passive"))
    )
    (net (code "76") (name "Net-(Relay4-NO)") (class "Default")
      (node (ref "P10") (pin "1") (pinfunction "1_1") (pintype "passive"))
      (node (ref "Relay4") (pin "4") (pinfunction "NO_4") (pintype "passive"))
    )
    (net (code "77") (name "Net-(Relay4-Pad1)") (class "Default")
      (node (ref "Relay4") (pin "1") (pinfunction "1_1") (pintype "passive"))
      (node (ref "U4") (pin "4") (pinfunction "C_4") (pintype "passive"))
    )
    (net (code "78") (name "Net-(Relay5-NC)") (class "Default")
      (node (ref "P11") (pin "1") (pinfunction "1_1") (pintype "passive"))
      (node (ref "Relay5") (pin "2") (pinfunction "NC_2") (pintype "passive"))
    )
    (net (code "79") (name "Net-(Relay5-NO)") (class "Default")
      (node (ref "P11") (pin "3") (pinfunction "3_3") (pintype "passive"))
      (node (ref "Relay5") (pin "4") (pinfunction "NO_4") (pintype "passive"))
    )
    (net (code "80") (name "Net-(Relay5-Pad1)") (class "Default")
      (node (ref "Relay5") (pin "1") (pinfunction "1_1") (pintype "passive"))
      (node (ref "U5") (pin "4") (pinfunction "C_4") (pintype "passive"))
    )
    (net (code "81") (name "Net-(Relay6-NC)") (class "Default")
      (node (ref "P13") (pin "3") (pinfunction "3_3") (pintype "passive"))
      (node (ref "Relay6") (pin "2") (pinfunction "NC_2") (pintype "passive"))
    )
    (net (code "82") (name "Net-(Relay6-NO)") (class "Default")
      (node (ref "P13") (pin "1") (pinfunction "1_1") (pintype "passive"))
      (node (ref "Relay6") (pin "4") (pinfunction "NO_4") (pintype "passive"))
    )
    (net (code "83") (name "Net-(Relay6-Pad1)") (class "Default")
      (node (ref "Relay6") (pin "1") (pinfunction "1_1") (pintype "passive"))
      (node (ref "U6") (pin "4") (pinfunction "C_4") (pintype "passive"))
    )
    (net (code "84") (name "Net-(Relay7-NC)") (class "Default")
      (node (ref "P17") (pin "1") (pinfunction "1_1") (pintype "passive"))
      (node (ref "Relay7") (pin "2") (pinfunction "NC_2") (pintype "passive"))
    )
    (net (code "85") (name "Net-(Relay7-NO)") (class "Default")
      (node (ref "P17") (pin "3") (pinfunction "3_3") (pintype "passive"))
      (node (ref "Relay7") (pin "4") (pinfunction "NO_4") (pintype "passive"))
    )
    (net (code "86") (name "Net-(Relay7-Pad1)") (class "Default")
      (node (ref "Relay7") (pin "1") (pinfunction "1_1") (pintype "passive"))
      (node (ref "U7") (pin "4") (pinfunction "C_4") (pintype "passive"))
    )
    (net (code "87") (name "Net-(Relay8-NC)") (class "Default")
      (node (ref "P19") (pin "3") (pinfunction "3_3") (pintype "passive"))
      (node (ref "Relay8") (pin "2") (pinfunction "NC_2") (pintype "passive"))
    )
    (net (code "88") (name "Net-(Relay8-NO)") (class "Default")
      (node (ref "P19") (pin "1") (pinfunction "1_1") (pintype "passive"))
      (node (ref "Relay8") (pin "4") (pinfunction "NO_4") (pintype "passive"))
    )
    (net (code "89") (name "Net-(Relay8-Pad1)") (class "Default")
      (node (ref "Relay8") (pin "1") (pinfunction "1_1") (pintype "passive"))
      (node (ref "U8") (pin "4") (pinfunction "C_4") (pintype "passive"))
    )
    (net (code "90") (name "Net-(Relay9-NC)") (class "Default")
      (node (ref "P20") (pin "1") (pinfunction "1_1") (pintype "passive"))
      (node (ref "Relay9") (pin "2") (pinfunction "NC_2") (pintype "passive"))
    )
    (net (code "91") (name "Net-(Relay9-NO)") (class "Default")
      (node (ref "P20") (pin "3") (pinfunction "3_3") (pintype "passive"))
      (node (ref "Relay9") (pin "4") (pinfunction "NO_4") (pintype "passive"))
    )
    (net (code "92") (name "Net-(Relay9-Pad1)") (class "Default")
      (node (ref "Relay9") (pin "1") (pinfunction "1_1") (pintype "passive"))
      (node (ref "U9") (pin "4") (pinfunction "C_4") (pintype "passive"))
    )
    (net (code "93") (name "Net-(Relay10-NC)") (class "Default")
      (node (ref "P22") (pin "3") (pinfunction "3_3") (pintype "passive"))
      (node (ref "Relay10") (pin "2") (pinfunction "NC_2") (pintype "passive"))
    )
    (net (code "94") (name "Net-(Relay10-NO)") (class "Default")
      (node (ref "P22") (pin "1") (pinfunction "1_1") (pintype "passive"))
      (node (ref "Relay10") (pin "4") (pinfunction "NO_4") (pintype "passive"))
    )
    (net (code "95") (name "Net-(Relay10-Pad1)") (class "Default")
      (node (ref "Relay10") (pin "1") (pinfunction "1_1") (pintype "passive"))
      (node (ref "U10") (pin "4") (pinfunction "C_4") (pintype "passive"))
    )
    (net (code "96") (name "Net-(Relay11-NC)") (class "Default")
      (node (ref "P23") (pin "1") (pinfunction "1_1") (pintype "passive"))
      (node (ref "Relay11") (pin "2") (pinfunction "NC_2") (pintype "passive"))
    )
    (net (code "97") (name "Net-(Relay11-NO)") (class "Default")
      (node (ref "P23") (pin "3") (pinfunction "3_3") (pintype "passive"))
      (node (ref "Relay11") (pin "4") (pinfunction "NO_4") (pintype "passive"))
    )
    (net (code "98") (name "Net-(Relay11-Pad1)") (class "Default")
      (node (ref "Relay11") (pin "1") (pinfunction "1_1") (pintype "passive"))
      (node (ref "U11") (pin "4") (pinfunction "C_4") (pintype "passive"))
    )
    (net (code "99") (name "Net-(Relay12-NC)") (class "Default")
      (node (ref "P25") (pin "3") (pinfunction "3_3") (pintype "passive"))
      (node (ref "Relay12") (pin "2") (pinfunction "NC_2") (pintype "passive"))
    )
    (net (code "100") (name "Net-(Relay12-NO)") (class "Default")
      (node (ref "P25") (pin "1") (pinfunction "1_1") (pintype "passive"))
      (node (ref "Relay12") (pin "4") (pinfunction "NO_4") (pintype "passive"))
    )
    (net (code "101") (name "Net-(Relay12-Pad1)") (class "Default")
      (node (ref "Relay12") (pin "1") (pinfunction "1_1") (pintype "passive"))
      (node (ref "U12") (pin "4") (pinfunction "C_4") (pintype "passive"))
    )
    (net (code "102") (name "Net-(Relay13-NC)") (class "Default")
      (node (ref "P28") (pin "1") (pinfunction "1_1") (pintype "passive"))
      (node (ref "Relay13") (pin "2") (pinfunction "NC_2") (pintype "passive"))
    )
    (net (code "103") (name "Net-(Relay13-NO)") (class "Default")
      (node (ref "P28") (pin "3") (pinfunction "3_3") (pintype "passive"))
      (node (ref "Relay13") (pin "4") (pinfunction "NO_4") (pintype "passive"))
    )
    (net (code "104") (name "Net-(Relay13-Pad1)") (class "Default")
      (node (ref "Relay13") (pin "1") (pinfunction "1_1") (pintype "passive"))
      (node (ref "U13") (pin "4") (pinfunction "C_4") (pintype "passive"))
    )
    (net (code "105") (name "Net-(Relay14-NC)") (class "Default")
      (node (ref "P30") (pin "3") (pinfunction "3_3") (pintype "passive"))
      (node (ref "Relay14") (pin "2") (pinfunction "NC_2") (pintype "passive"))
    )
    (net (code "106") (name "Net-(Relay14-NO)") (class "Default")
      (node (ref "P30") (pin "1") (pinfunction "1_1") (pintype "passive"))
      (node (ref "Relay14") (pin "4") (pinfunction "NO_4") (pintype "passive"))
    )
    (net (code "107") (name "Net-(Relay14-Pad1)") (class "Default")
      (node (ref "Relay14") (pin "1") (pinfunction "1_1") (pintype "passive"))
      (node (ref "U14") (pin "4") (pinfunction "C_4") (pintype "passive"))
    )
    (net (code "108") (name "Net-(Relay15-NC)") (class "Default")
      (node (ref "P31") (pin "1") (pinfunction "1_1") (pintype "passive"))
      (node (ref "Relay15") (pin "2") (pinfunction "NC_2") (pintype "passive"))
    )
    (net (code "109") (name "Net-(Relay15-NO)") (class "Default")
      (node (ref "P31") (pin "3") (pinfunction "3_3") (pintype "passive"))
      (node (ref "Relay15") (pin "4") (pinfunction "NO_4") (pintype "passive"))
    )
    (net (code "110") (name "Net-(Relay15-Pad1)") (class "Default")
      (node (ref "Relay15") (pin "1") (pinfunction "1_1") (pintype "passive"))
      (node (ref "U15") (pin "4") (pinfunction "C_4") (pintype "passive"))
    )
    (net (code "111") (name "Net-(Relay16-NC)") (class "Default")
      (node (ref "P33") (pin "3") (pinfunction "3_3") (pintype "passive"))
      (node (ref "Relay16") (pin "2") (pinfunction "NC_2") (pintype "passive"))
    )
    (net (code "112") (name "Net-(Relay16-NO)") (class "Default")
      (node (ref "P33") (pin "1") (pinfunction "1_1") (pintype "passive"))
      (node (ref "Relay16") (pin "4") (pinfunction "NO_4") (pintype "passive"))
    )
    (net (code "113") (name "Net-(Relay16-Pad1)") (class "Default")
      (node (ref "Relay16") (pin "1") (pinfunction "1_1") (pintype "passive"))
      (node (ref "U16") (pin "4") (pinfunction "C_4") (pintype "passive"))
    )
    (net (code "114") (name "Net-(U1-A)") (class "Default")
      (node (ref "R1") (pin "2") (pinfunction "2_2") (pintype "passive"))
      (node (ref "U1") (pin "1") (pinfunction "A_1") (pintype "passive"))
    )
    (net (code "115") (name "Net-(U2-A)") (class "Default")
      (node (ref "R2") (pin "2") (pinfunction "2_2") (pintype "passive"))
      (node (ref "U2") (pin "1") (pinfunction "A_1") (pintype "passive"))
    )
    (net (code "116") (name "Net-(U3-A)") (class "Default")
      (node (ref "R3") (pin "2") (pinfunction "2_2") (pintype "passive"))
      (node (ref "U3") (pin "1") (pinfunction "A_1") (pintype "passive"))
    )
    (net (code "117") (name "Net-(U4-A)") (class "Default")
      (node (ref "R4") (pin "2") (pinfunction "2_2") (pintype "passive"))
      (node (ref "U4") (pin "1") (pinfunction "A_1") (pintype "passive"))
    )
    (net (code "118") (name "Net-(U5-A)") (class "Default")
      (node (ref "R5") (pin "2") (pinfunction "2_2") (pintype "passive"))
      (node (ref "U5") (pin "1") (pinfunction "A_1") (pintype "passive"))
    )
    (net (code "119") (name "Net-(U6-A)") (class "Default")
      (node (ref "R6") (pin "2") (pinfunction "2_2") (pintype "passive"))
      (node (ref "U6") (pin "1") (pinfunction "A_1") (pintype "passive"))
    )
    (net (code "120") (name "Net-(U7-A)") (class "Default")
      (node (ref "R13") (pin "2") (pinfunction "2_2") (pintype "passive"))
      (node (ref "U7") (pin "1") (pinfunction "A_1") (pintype "passive"))
    )
    (net (code "121") (name "Net-(U8-A)") (class "Default")
      (node (ref "R14") (pin "2") (pinfunction "2_2") (pintype "passive"))
      (node (ref "U8") (pin "1") (pinfunction "A_1") (pintype "passive"))
    )
    (net (code "122") (name "Net-(U9-A)") (class "Default")
      (node (ref "R15") (pin "2") (pinfunction "2_2") (pintype "passive"))
      (node (ref "U9") (pin "1") (pinfunction "A_1") (pintype "passive"))
    )
    (net (code "123") (name "Net-(U10-A)") (class "Default")
      (node (ref "R16") (pin "2") (pinfunction "2_2") (pintype "passive"))
      (node (ref "U10") (pin "1") (pinfunction "A_1") (pintype "passive"))
    )
    (net (code "124") (name "Net-(U11-A)") (class "Default")
      (node (ref "R17") (pin "2") (pinfunction "2_2") (pintype "passive"))
      (node (ref "U11") (pin "1") (pinfunction "A_1") (pintype "passive"))
    )
    (net (code "125") (name "Net-(U12-A)") (class "Default")
      (node (ref "R18") (pin "2") (pinfunction "2_2") (pintype "passive"))
      (node (ref "U12") (pin "1") (pinfunction "A_1") (pintype "passive"))
    )
    (net (code "126") (name "Net-(U13-A)") (class "Default")
      (node (ref "R25") (pin "2") (pinfunction "2_2") (pintype "passive"))
      (node (ref "U13") (pin "1") (pinfunction "A_1") (pintype "passive"))
    )
    (net (code "127") (name "Net-(U14-A)") (class "Default")
      (node (ref "R26") (pin "2") (pinfunction "2_2") (pintype "passive"))
      (node (ref "U14") (pin "1") (pinfunction "A_1") (pintype "passive"))
    )
    (net (code "128") (name "Net-(U15-A)") (class "Default")
      (node (ref "R27") (pin "2") (pinfunction "2_2") (pintype "passive"))
      (node (ref "U15") (pin "1") (pinfunction "A_1") (pintype "passive"))
    )
    (net (code "129") (name "Net-(U16-A)") (class "Default")
      (node (ref "R28") (pin "2") (pinfunction "2_2") (pintype "passive"))
      (node (ref "U16") (pin "1") (pinfunction "A_1") (pintype "passive"))
    )
    (net (code "130") (name "VCC") (class "Default")
      (node (ref "C1") (pin "2") (pinfunction "2_2") (pintype "passive"))
      (node (ref "D1") (pin "2") (pinfunction "K_2") (pintype "passive"))
      (node (ref "P1") (pin "2") (pinfunction "2_2") (pintype "passive"))
      (node (ref "Relay1") (pin "8") (pinfunction "8_8") (pintype "passive"))
      (node (ref "Relay10") (pin "8") (pinfunction "8_8") (pintype "passive"))
      (node (ref "Relay11") (pin "8") (pinfunction "8_8") (pintype "passive"))
      (node (ref "Relay12") (pin "8") (pinfunction "8_8") (pintype "passive"))
      (node (ref "Relay13") (pin "8") (pinfunction "8_8") (pintype "passive"))
      (node (ref "Relay14") (pin "8") (pinfunction "8_8") (pintype "passive"))
      (node (ref "Relay15") (pin "8") (pinfunction "8_8") (pintype "passive"))
      (node (ref "Relay16") (pin "8") (pinfunction "8_8") (pintype "passive"))
      (node (ref "Relay2") (pin "8") (pinfunction "8_8") (pintype "passive"))
      (node (ref "Relay3") (pin "8") (pinfunction "8_8") (pintype "passive"))
      (node (ref "Relay4") (pin "8") (pinfunction "8_8") (pintype "passive"))
      (node (ref "Relay5") (pin "8") (pinfunction "8_8") (pintype "passive"))
      (node (ref "Relay6") (pin "8") (pinfunction "8_8") (pintype "passive"))
      (node (ref "Relay7") (pin "8") (pinfunction "8_8") (pintype "passive"))
      (node (ref "Relay8") (pin "8") (pinfunction "8_8") (pintype "passive"))
      (node (ref "Relay9") (pin "8") (pinfunction "8_8") (pintype "passive"))
    )
    (net (code "131") (name "unconnected-(Relay1-Pad5)") (class "Default")
      (node (ref "Relay1") (pin "5") (pinfunction "5_5") (pintype "passive"))
    )
    (net (code "132") (name "unconnected-(Relay1-Pad6)") (class "Default")
      (node (ref "Relay1") (pin "6") (pinfunction "6_6") (pintype "passive"))
    )
    (net (code "133") (name "unconnected-(Relay1-Pad7)") (class "Default")
      (node (ref "Relay1") (pin "7") (pinfunction "7_7") (pintype "passive"))
    )
    (net (code "134") (name "unconnected-(Relay2-Pad5)") (class "Default")
      (node (ref "Relay2") (pin "5") (pinfunction "5_5") (pintype "passive"))
    )
    (net (code "135") (name "unconnected-(Relay2-Pad6)") (class "Default")
      (node (ref "Relay2") (pin "6") (pinfunction "6_6") (pintype "passive"))
    )
    (net (code "136") (name "unconnected-(Relay2-Pad7)") (class "Default")
      (node (ref "Relay2") (pin "7") (pinfunction "7_7") (pintype "passive"))
    )
    (net (code "137") (name "unconnected-(Relay3-Pad5)") (class "Default")
      (node (ref "Relay3") (pin "5") (pinfunction "5_5") (pintype "passive"))
    )
    (net (code "138") (name "unconnected-(Relay3-Pad6)") (class "Default")
      (node (ref "Relay3") (pin "6") (pinfunction "6_6") (pintype "passive"))
    )
    (net (code "139") (name "unconnected-(Relay3-Pad7)") (class "Default")
      (node (ref "Relay3") (pin "7") (pinfunction "7_7") (pintype "passive"))
    )
    (net (code "140") (name "unconnected-(Relay4-Pad5)") (class "Default")
      (node (ref "Relay4") (pin "5") (pinfunction "5_5") (pintype "passive"))
    )
    (net (code "141") (name "unconnected-(Relay4-Pad6)") (class "Default")
      (node (ref "Relay4") (pin "6") (pinfunction "6_6") (pintype "passive"))
    )
    (net (code "142") (name "unconnected-(Relay4-Pad7)") (class "Default")
      (node (ref "Relay4") (pin "7") (pinfunction "7_7") (pintype "passive"))
    )
    (net (code "143") (name "unconnected-(Relay5-Pad5)") (class "Default")
      (node (ref "Relay5") (pin "5") (pinfunction "5_5") (pintype "passive"))
    )
    (net (code "144") (name "unconnected-(Relay5-Pad6)") (class "Default")
      (node (ref "Relay5") (pin "6") (pinfunction "6_6") (pintype "passive"))
    )
    (net (code "145") (name "unconnected-(Relay5-Pad7)") (class "Default")
      (node (ref "Relay5") (pin "7") (pinfunction "7_7") (pintype "passive"))
    )
    (net (code "146") (name "unconnected-(Relay6-Pad5)") (class "Default")
      (node (ref "Relay6") (pin "5") (pinfunction "5_5") (pintype "passive"))
    )
    (net (code "147") (name "unconnected-(Relay6-Pad6)") (class "Default")
      (node (ref "Relay6") (pin "6") (pinfunction "6_6") (pintype "passive"))
    )
    (net (code "148") (name "unconnected-(Relay6-Pad7)") (class "Default")
      (node (ref "Relay6") (pin "7") (pinfunction "7_7") (pintype "passive"))
    )
    (net (code "149") (name "unconnected-(Relay7-Pad5)") (class "Default")
      (node (ref "Relay7") (pin "5") (pinfunction "5_5") (pintype "passive"))
    )
    (net (code "150") (name "unconnected-(Relay7-Pad6)") (class "Default")
      (node (ref "Relay7") (pin "6") (pinfunction "6_6") (pintype "passive"))
    )
    (net (code "151") (name "unconnected-(Relay7-Pad7)") (class "Default")
      (node (ref "Relay7") (pin "7") (pinfunction "7_7") (pintype "passive"))
    )
    (net (code "152") (name "unconnected-(Relay8-Pad5)") (class "Default")
      (node (ref "Relay8") (pin "5") (pinfunction "5_5") (pintype "passive"))
    )
    (net (code "153") (name "unconnected-(Relay8-Pad6)") (class "Default")
      (node (ref "Relay8") (pin "6") (pinfunction "6_6") (pintype "passive"))
    )
    (net (code "154") (name "unconnected-(Relay8-Pad7)") (class "Default")
      (node (ref "Relay8") (pin "7") (pinfunction "7_7") (pintype "passive"))
    )
    (net (code "155") (name "unconnected-(Relay9-Pad5)") (class "Default")
      (node (ref "Relay9") (pin "5") (pinfunction "5_5") (pintype "passive"))
    )
    (net (code "156") (name "unconnected-(Relay9-Pad6)") (class "Default")
      (node (ref "Relay9") (pin "6") (pinfunction "6_6") (pintype "passive"))
    )
    (net (code "157") (name "unconnected-(Relay9-Pad7)") (class "Default")
      (node (ref "Relay9") (pin "7") (pinfunction "7_7") (pintype "passive"))
    )
    (net (code "158") (name "unconnected-(Relay10-Pad5)") (class "Default")
      (node (ref "Relay10") (pin "5") (pinfunction "5_5") (pintype "passive"))
    )
    (net (code "159") (name "unconnected-(Relay10-Pad6)") (class "Default")
      (node (ref "Relay10") (pin "6") (pinfunction "6_6") (pintype "passive"))
    )
    (net (code "160") (name "unconnected-(Relay10-Pad7)") (class "Default")
      (node (ref "Relay10") (pin "7") (pinfunction "7_7") (pintype "passive"))
    )
    (net (code "161") (name "unconnected-(Relay11-Pad5)") (class "Default")
      (node (ref "Relay11") (pin "5") (pinfunction "5_5") (pintype "passive"))
    )
    (net (code "162") (name "unconnected-(Relay11-Pad6)") (class "Default")
      (node (ref "Relay11") (pin "6") (pinfunction "6_6") (pintype "passive"))
    )
    (net (code "163") (name "unconnected-(Relay11-Pad7)") (class "Default")
      (node (ref "Relay11") (pin "7") (pinfunction "7_7") (pintype "passive"))
    )
    (net (code "164") (name "unconnected-(Relay12-Pad5)") (class "Default")
      (node (ref "Relay12") (pin "5") (pinfunction "5_5") (pintype "passive"))
    )
    (net (code "165") (name "unconnected-(Relay12-Pad6)") (class "Default")
      (node (ref "Relay12") (pin "6") (pinfunction "6_6") (pintype "passive"))
    )
    (net (code "166") (name "unconnected-(Relay12-Pad7)") (class "Default")
      (node (ref "Relay12") (pin "7") (pinfunction "7_7") (pintype "passive"))
    )
    (net (code "167") (name "unconnected-(Relay13-Pad5)") (class "Default")
      (node (ref "Relay13") (pin "5") (pinfunction "5_5") (pintype "passive"))
    )
    (net (code "168") (name "unconnected-(Relay13-Pad6)") (class "Default")
      (node (ref "Relay13") (pin "6") (pinfunction "6_6") (pintype "passive"))
    )
    (net (code "169") (name "unconnected-(Relay13-Pad7)") (class "Default")
      (node (ref "Relay13") (pin "7") (pinfunction "7_7") (pintype "passive"))
    )
    (net (code "170") (name "unconnected-(Relay14-Pad5)") (class "Default")
      (node (ref "Relay14") (pin "5") (pinfunction "5_5") (pintype "passive"))
    )
    (net (code "171") (name "unconnected-(Relay14-Pad6)") (class "Default")
      (node (ref "Relay14") (pin "6") (pinfunction "6_6") (pintype "passive"))
    )
    (net (code "172") (name "unconnected-(Relay14-Pad7)") (class "Default")
      (node (ref "Relay14") (pin "7") (pinfunction "7_7") (pintype "passive"))
    )
    (net (code "173") (name "unconnected-(Relay15-Pad5)") (class "Default")
      (node (ref "Relay15") (pin "5") (pinfunction "5_5") (pintype "passive"))
    )
    (net (code "174") (name "unconnected-(Relay15-Pad6)") (class "Default")
      (node (ref "Relay15") (pin "6") (pinfunction "6_6") (pintype "passive"))
    )
    (net (code "175") (name "unconnected-(Relay15-Pad7)") (class "Default")
      (node (ref "Relay15") (pin "7") (pinfunction "7_7") (pintype "passive"))
    )
    (net (code "176") (name "unconnected-(Relay16-Pad5)") (class "Default")
      (node (ref "Relay16") (pin "5") (pinfunction "5_5") (pintype "passive"))
    )
    (net (code "177") (name "unconnected-(Relay16-Pad6)") (class "Default")
      (node (ref "Relay16") (pin "6") (pinfunction "6_6") (pintype "passive"))
    )
    (net (code "178") (name "unconnected-(Relay16-Pad7)") (class "Default")
      (node (ref "Relay16") (pin "7") (pinfunction "7_7") (pintype "passive"))
    )
  )
)
